# joy-button-pcb.net
KiCad netlist of a schematic drawn in EAGLE
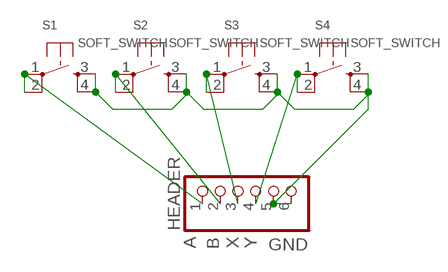
[diagram p0: schematic, sheet 1]

(export (version "E")
  (design (tool "Eeschema 10.0.6"))
  (components
    (comp (ref "HEADER")
      (value "PINHD-1X6")
      (footprint "eagle-import:1X06")
      (libsource (lib "eagle-import") (part "PINHD-1X6"))
    )
    (comp (ref "S1")
      (value "SOFT_SWITCH")
      (footprint "eagle-import:8MM_SWITCH")
      (libsource (lib "eagle-import") (part "SOFT_SWITCH"))
    )
    (comp (ref "S2")
      (value "SOFT_SWITCH")
      (footprint "eagle-import:8MM_SWITCH")
      (libsource (lib "eagle-import") (part "SOFT_SWITCH"))
    )
    (comp (ref "S3")
      (value "SOFT_SWITCH")
      (footprint "eagle-import:8MM_SWITCH")
      (libsource (lib "eagle-import") (part "SOFT_SWITCH"))
    )
    (comp (ref "S4")
      (value "SOFT_SWITCH")
      (footprint "eagle-import:8MM_SWITCH")
      (libsource (lib "eagle-import") (part "SOFT_SWITCH"))
    )
  )
  (nets
    (net (code "1") (name "/A") (class "Default")
      (node (ref "HEADER") (pin "1") (pinfunction "1_1") (pintype "passive"))
      (node (ref "S1") (pin "1") (pinfunction "P_1") (pintype "passive"))
      (node (ref "S1") (pin "2") (pinfunction "P1_2") (pintype "passive"))
    )
    (net (code "2") (name "/B") (class "Default")
      (node (ref "HEADER") (pin "2") (pinfunction "2_2") (pintype "passive"))
      (node (ref "S2") (pin "1") (pinfunction "P_1") (pintype "passive"))
      (node (ref "S2") (pin "2") (pinfunction "P1_2") (pintype "passive"))
    )
    (net (code "3") (name "/GND") (class "Default")
      (node (ref "HEADER") (pin "5") (pinfunction "5_5") (pintype "passive"))
      (node (ref "HEADER") (pin "6") (pinfunction "6_6") (pintype "passive"))
      (node (ref "S1") (pin "3") (pinfunction "S_3") (pintype "passive"))
      (node (ref "S1") (pin "4") (pinfunction "S1_4") (pintype "passive"))
      (node (ref "S2") (pin "3") (pinfunction "S_3") (pintype "passive"))
      (node (ref "S2") (pin "4") (pinfunction "S1_4") (pintype "passive"))
      (node (ref "S3") (pin "3") (pinfunction "S_3") (pintype "passive"))
      (node (ref "S3") (pin "4") (pinfunction "S1_4") (pintype "passive"))
      (node (ref "S4") (pin "3") (pinfunction "S_3") (pintype "passive"))
      (node (ref "S4") (pin "4") (pinfunction "S1_4") (pintype "passive"))
    )
    (net (code "4") (name "/X") (class "Default")
      (node (ref "HEADER") (pin "3") (pinfunction "3_3") (pintype "passive"))
      (node (ref "S3") (pin "1") (pinfunction "P_1") (pintype "passive"))
      (node (ref "S3") (pin "2") (pinfunction "P1_2") (pintype "passive"))
    )
    (net (code "5") (name "/Y") (class "Default")
      (node (ref "HEADER") (pin "4") (pinfunction "4_4") (pintype "passive"))
      (node (ref "S4") (pin "1") (pinfunction "P_1") (pintype "passive"))
      (node (ref "S4") (pin "2") (pinfunction "P1_2") (pintype "passive"))
    )
  )
)
